# ESP32.net
KiCad netlist of a schematic drawn in Altium Designer
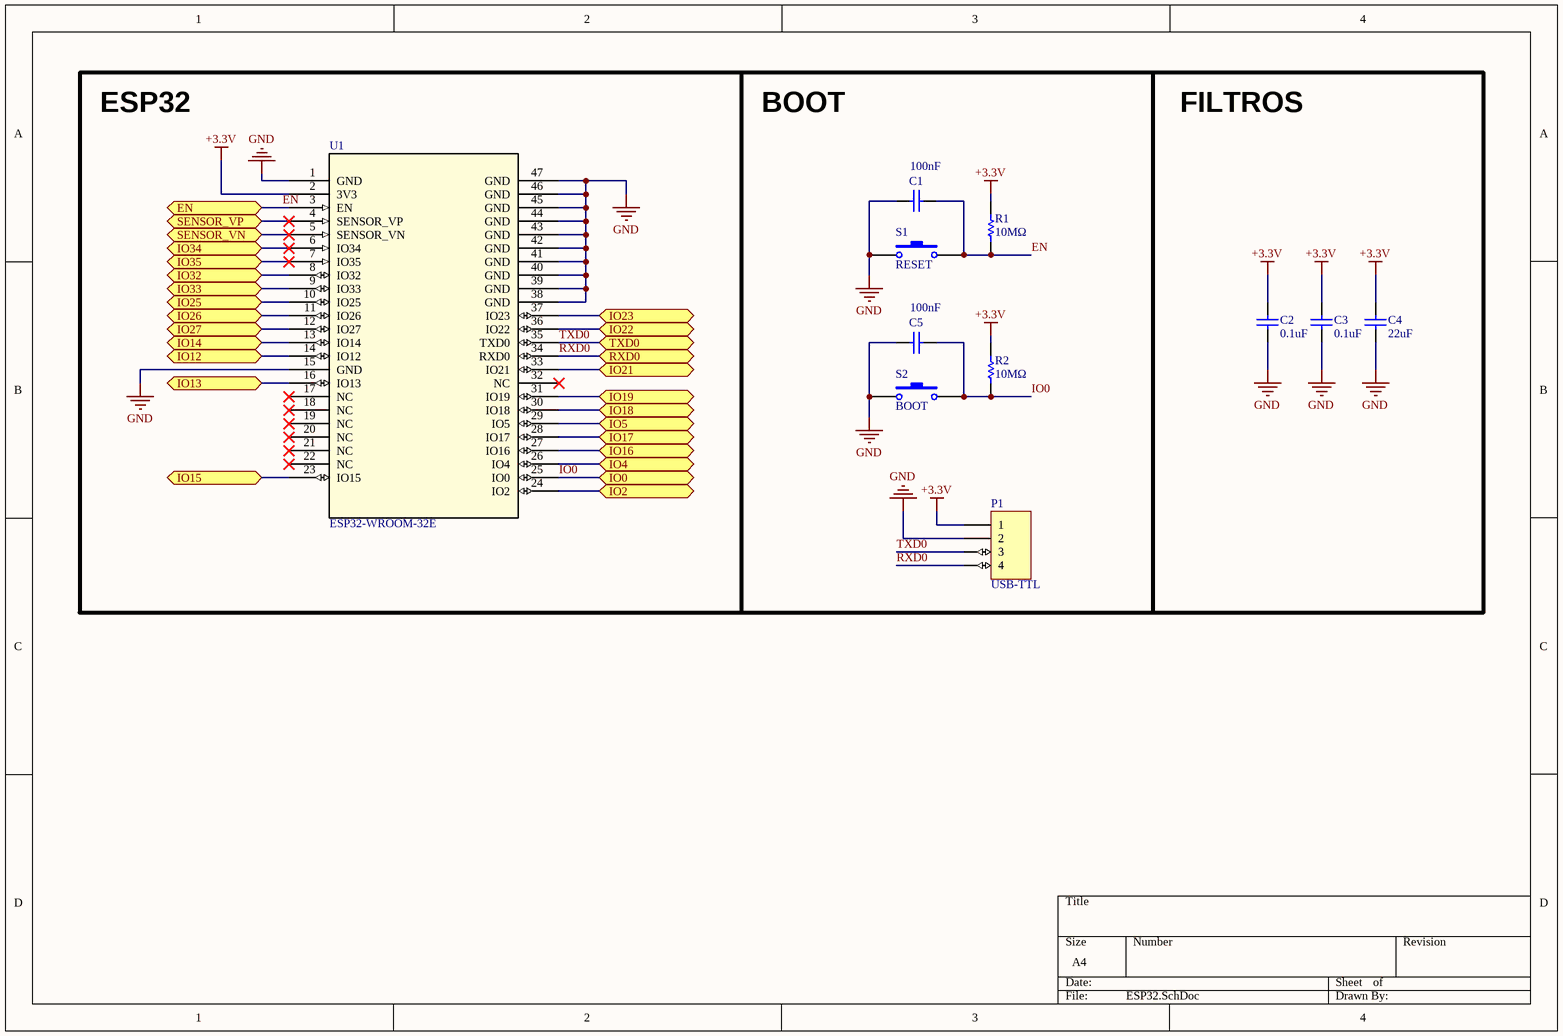
[diagram p0: ESP32.SchDoc]

(export (version "E")
  (design (tool "Eeschema 10.0.6"))
  (components
    (comp (ref "C1")
      (value "100nF")
      (footprint "CAPC2012N")
      (description "Capacitor")
      (fields (field (name "PUBLISHER") "Altium Limited"))
      (libsource (lib "Miscellaneous Devices") (part "Cap"))
    )
    (comp (ref "C2")
      (value "0.1uF")
      (footprint "CAPC2012N")
      (description "Capacitor")
      (fields (field (name "PUBLISHER") "Altium Limited"))
      (libsource (lib "Miscellaneous Devices") (part "Cap"))
    )
    (comp (ref "C3")
      (value "0.1uF")
      (footprint "CAPC2012N")
      (description "Capacitor")
      (fields (field (name "PUBLISHER") "Altium Limited"))
      (libsource (lib "Miscellaneous Devices") (part "Cap"))
    )
    (comp (ref "C4")
      (value "22uF")
      (footprint "CAPC2012N")
      (description "Capacitor")
      (fields (field (name "PUBLISHER") "Altium Limited"))
      (libsource (lib "Miscellaneous Devices") (part "Cap"))
    )
    (comp (ref "C5")
      (value "100nF")
      (footprint "CAPC2012N")
      (description "Capacitor")
      (fields (field (name "PUBLISHER") "Altium Limited"))
      (libsource (lib "Miscellaneous Devices") (part "Cap"))
    )
    (comp (ref "P1")
      (value "USB-TTL")
      (footprint "CONNHDR_1X4_2.54MM")
      (description "Header, 4-Pin")
      (fields (field (name "PUBLISHER") "Altium Limited"))
      (libsource (lib "Miscellaneous Connectors") (part "MHDR1X4"))
    )
    (comp (ref "R1")
      (value "10MΩ")
      (footprint "RESC2012N")
      (description "Resistor")
      (fields (field (name "PUBLISHER") "Altium Limited"))
      (libsource (lib "Miscellaneous Devices") (part "Res1"))
    )
    (comp (ref "R2")
      (value "10MΩ")
      (footprint "RESC2012N")
      (description "Resistor")
      (fields (field (name "PUBLISHER") "Altium Limited"))
      (libsource (lib "Miscellaneous Devices") (part "Res1"))
    )
    (comp (ref "S1")
      (value "RESET")
      (footprint "SWITCH TACTILE SPST-NO 0.05A 12V")
      (description "Switch")
      (fields (field (name "PUBLISHER") "Altium Limited"))
      (libsource (lib "Miscellaneous Devices") (part "SW-PB"))
    )
    (comp (ref "S2")
      (value "BOOT")
      (footprint "SWITCH TACTILE SPST-NO 0.05A 12V")
      (description "Switch")
      (fields (field (name "PUBLISHER") "Altium Limited"))
      (libsource (lib "Miscellaneous Devices") (part "SW-PB"))
    )
    (comp (ref "U1")
      (value "ESP32-WROOM-32E")
      (footprint "ESP32-WROOM-32E")
      (libsource (lib "MH_lib") (part "ESP32-WROOM-32E"))
    )
  )
  (nets
    (net (code "1") (name "+3.3V") (class "Default")
      (node (ref "C2") (pin "1") (pinfunction "1_1") (pintype "passive"))
      (node (ref "C3") (pin "1") (pinfunction "1_1") (pintype "passive"))
      (node (ref "C4") (pin "1") (pinfunction "1_1") (pintype "passive"))
      (node (ref "P1") (pin "1") (pinfunction "1_1") (pintype "passive"))
      (node (ref "R1") (pin "2") (pinfunction "2_2") (pintype "passive"))
      (node (ref "R2") (pin "2") (pinfunction "2_2") (pintype "passive"))
      (node (ref "U1") (pin "2") (pinfunction "3V3_2") (pintype "power_in"))
    )
    (net (code "2") (name "/EN") (class "Default")
      (node (ref "C1") (pin "1") (pinfunction "1_1") (pintype "passive"))
      (node (ref "R1") (pin "1") (pinfunction "1_1") (pintype "passive"))
      (node (ref "S1") (pin "2") (pinfunction "2_2") (pintype "passive"))
      (node (ref "U1") (pin "3") (pinfunction "EN_3") (pintype "input"))
    )
    (net (code "3") (name "/IO0") (class "Default")
      (node (ref "C5") (pin "1") (pinfunction "1_1") (pintype "passive"))
      (node (ref "R2") (pin "1") (pinfunction "1_1") (pintype "passive"))
      (node (ref "S2") (pin "2") (pinfunction "2_2") (pintype "passive"))
      (node (ref "U1") (pin "25") (pinfunction "IO0_25") (pintype "bidirectional"))
    )
    (net (code "4") (name "/IO2") (class "Default")
      (node (ref "U1") (pin "24") (pinfunction "IO2_24") (pintype "bidirectional"))
    )
    (net (code "5") (name "/IO4") (class "Default")
      (node (ref "U1") (pin "26") (pinfunction "IO4_26") (pintype "bidirectional"))
    )
    (net (code "6") (name "/IO5") (class "Default")
      (node (ref "U1") (pin "29") (pinfunction "IO5_29") (pintype "bidirectional"))
    )
    (net (code "7") (name "/IO12") (class "Default")
      (node (ref "U1") (pin "14") (pinfunction "IO12_14") (pintype "bidirectional"))
    )
    (net (code "8") (name "/IO13") (class "Default")
      (node (ref "U1") (pin "16") (pinfunction "IO13_16") (pintype "bidirectional"))
    )
    (net (code "9") (name "/IO14") (class "Default")
      (node (ref "U1") (pin "13") (pinfunction "IO14_13") (pintype "bidirectional"))
    )
    (net (code "10") (name "/IO15") (class "Default")
      (node (ref "U1") (pin "23") (pinfunction "IO15_23") (pintype "bidirectional"))
    )
    (net (code "11") (name "/IO16") (class "Default")
      (node (ref "U1") (pin "27") (pinfunction "IO16_27") (pintype "bidirectional"))
    )
    (net (code "12") (name "/IO17") (class "Default")
      (node (ref "U1") (pin "28") (pinfunction "IO17_28") (pintype "bidirectional"))
    )
    (net (code "13") (name "/IO18") (class "Default")
      (node (ref "U1") (pin "30") (pinfunction "IO18_30") (pintype "bidirectional"))
    )
    (net (code "14") (name "/IO19") (class "Default")
      (node (ref "U1") (pin "31") (pinfunction "IO19_31") (pintype "bidirectional"))
    )
    (net (code "15") (name "/IO21") (class "Default")
      (node (ref "U1") (pin "33") (pinfunction "IO21_33") (pintype "bidirectional"))
    )
    (net (code "16") (name "/IO22") (class "Default")
      (node (ref "U1") (pin "36") (pinfunction "IO22_36") (pintype "bidirectional"))
    )
    (net (code "17") (name "/IO23") (class "Default")
      (node (ref "U1") (pin "37") (pinfunction "IO23_37") (pintype "bidirectional"))
    )
    (net (code "18") (name "/IO25") (class "Default")
      (node (ref "U1") (pin "10") (pinfunction "IO25_10") (pintype "bidirectional"))
    )
    (net (code "19") (name "/IO26") (class "Default")
      (node (ref "U1") (pin "11") (pinfunction "IO26_11") (pintype "bidirectional"))
    )
    (net (code "20") (name "/IO27") (class "Default")
      (node (ref "U1") (pin "12") (pinfunction "IO27_12") (pintype "bidirectional"))
    )
    (net (code "21") (name "/IO32") (class "Default")
      (node (ref "U1") (pin "8") (pinfunction "IO32_8") (pintype "bidirectional"))
    )
    (net (code "22") (name "/IO33") (class "Default")
      (node (ref "U1") (pin "9") (pinfunction "IO33_9") (pintype "bidirectional"))
    )
    (net (code "23") (name "/IO34") (class "Default")
      (node (ref "U1") (pin "6") (pinfunction "IO34_6") (pintype "input+no_connect"))
    )
    (net (code "24") (name "/IO35") (class "Default")
      (node (ref "U1") (pin "7") (pinfunction "IO35_7") (pintype "input+no_connect"))
    )
    (net (code "25") (name "/RXD0") (class "Default")
      (node (ref "P1") (pin "4") (pinfunction "4_4") (pintype "bidirectional"))
      (node (ref "U1") (pin "34") (pinfunction "RXD0_34") (pintype "bidirectional"))
    )
    (net (code "26") (name "/SENSOR_VN") (class "Default")
      (node (ref "U1") (pin "5") (pinfunction "SENSOR_VN_5") (pintype "input+no_connect"))
    )
    (net (code "27") (name "/SENSOR_VP") (class "Default")
      (node (ref "U1") (pin "4") (pinfunction "SENSOR_VP_4") (pintype "input+no_connect"))
    )
    (net (code "28") (name "/TXD0") (class "Default")
      (node (ref "P1") (pin "3") (pinfunction "3_3") (pintype "bidirectional"))
      (node (ref "U1") (pin "35") (pinfunction "TXD0_35") (pintype "bidirectional"))
    )
    (net (code "29") (name "GND") (class "Default")
      (node (ref "C1") (pin "2") (pinfunction "2_2") (pintype "passive"))
      (node (ref "C2") (pin "2") (pinfunction "2_2") (pintype "passive"))
      (node (ref "C3") (pin "2") (pinfunction "2_2") (pintype "passive"))
      (node (ref "C4") (pin "2") (pinfunction "2_2") (pintype "passive"))
      (node (ref "C5") (pin "2") (pinfunction "2_2") (pintype "passive"))
      (node (ref "P1") (pin "2") (pinfunction "2_2") (pintype "passive"))
      (node (ref "S1") (pin "1") (pinfunction "1_1") (pintype "passive"))
      (node (ref "S2") (pin "1") (pinfunction "1_1") (pintype "passive"))
      (node (ref "U1") (pin "1") (pinfunction "GND_1") (pintype "power_in"))
      (node (ref "U1") (pin "15") (pinfunction "GND_15") (pintype "power_in"))
      (node (ref "U1") (pin "38") (pinfunction "GND_38") (pintype "power_in"))
      (node (ref "U1") (pin "39") (pinfunction "GND_39") (pintype "power_in"))
      (node (ref "U1") (pin "40") (pinfunction "GND_40") (pintype "power_in"))
      (node (ref "U1") (pin "41") (pinfunction "GND_41") (pintype "power_in"))
      (node (ref "U1") (pin "42") (pinfunction "GND_42") (pintype "power_in"))
      (node (ref "U1") (pin "43") (pinfunction "GND_43") (pintype "power_in"))
      (node (ref "U1") (pin "44") (pinfunction "GND_44") (pintype "power_in"))
      (node (ref "U1") (pin "45") (pinfunction "GND_45") (pintype "power_in"))
      (node (ref "U1") (pin "46") (pinfunction "GND_46") (pintype "power_in"))
      (node (ref "U1") (pin "47") (pinfunction "GND_47") (pintype "power_in"))
    )
    (net (code "30") (name "unconnected-(U1-NC-Pad17)") (class "Default")
      (node (ref "U1") (pin "17") (pinfunction "NC_17") (pintype "passive+no_connect"))
    )
    (net (code "31") (name "unconnected-(U1-NC-Pad18)") (class "Default")
      (node (ref "U1") (pin "18") (pinfunction "NC_18") (pintype "passive+no_connect"))
    )
    (net (code "32") (name "unconnected-(U1-NC-Pad19)") (class "Default")
      (node (ref "U1") (pin "19") (pinfunction "NC_19") (pintype "passive+no_connect"))
    )
    (net (code "33") (name "unconnected-(U1-NC-Pad20)") (class "Default")
      (node (ref "U1") (pin "20") (pinfunction "NC_20") (pintype "passive+no_connect"))
    )
    (net (code "34") (name "unconnected-(U1-NC-Pad21)") (class "Default")
      (node (ref "U1") (pin "21") (pinfunction "NC_21") (pintype "passive+no_connect"))
    )
    (net (code "35") (name "unconnected-(U1-NC-Pad22)") (class "Default")
      (node (ref "U1") (pin "22") (pinfunction "NC_22") (pintype "passive+no_connect"))
    )
    (net (code "36") (name "unconnected-(U1-NC-Pad32)") (class "Default")
      (node (ref "U1") (pin "32") (pinfunction "NC_32") (pintype "passive+no_connect"))
    )
  )
)
